# Railbooster_Shield.net
KiCad netlist of a schematic drawn in EAGLE
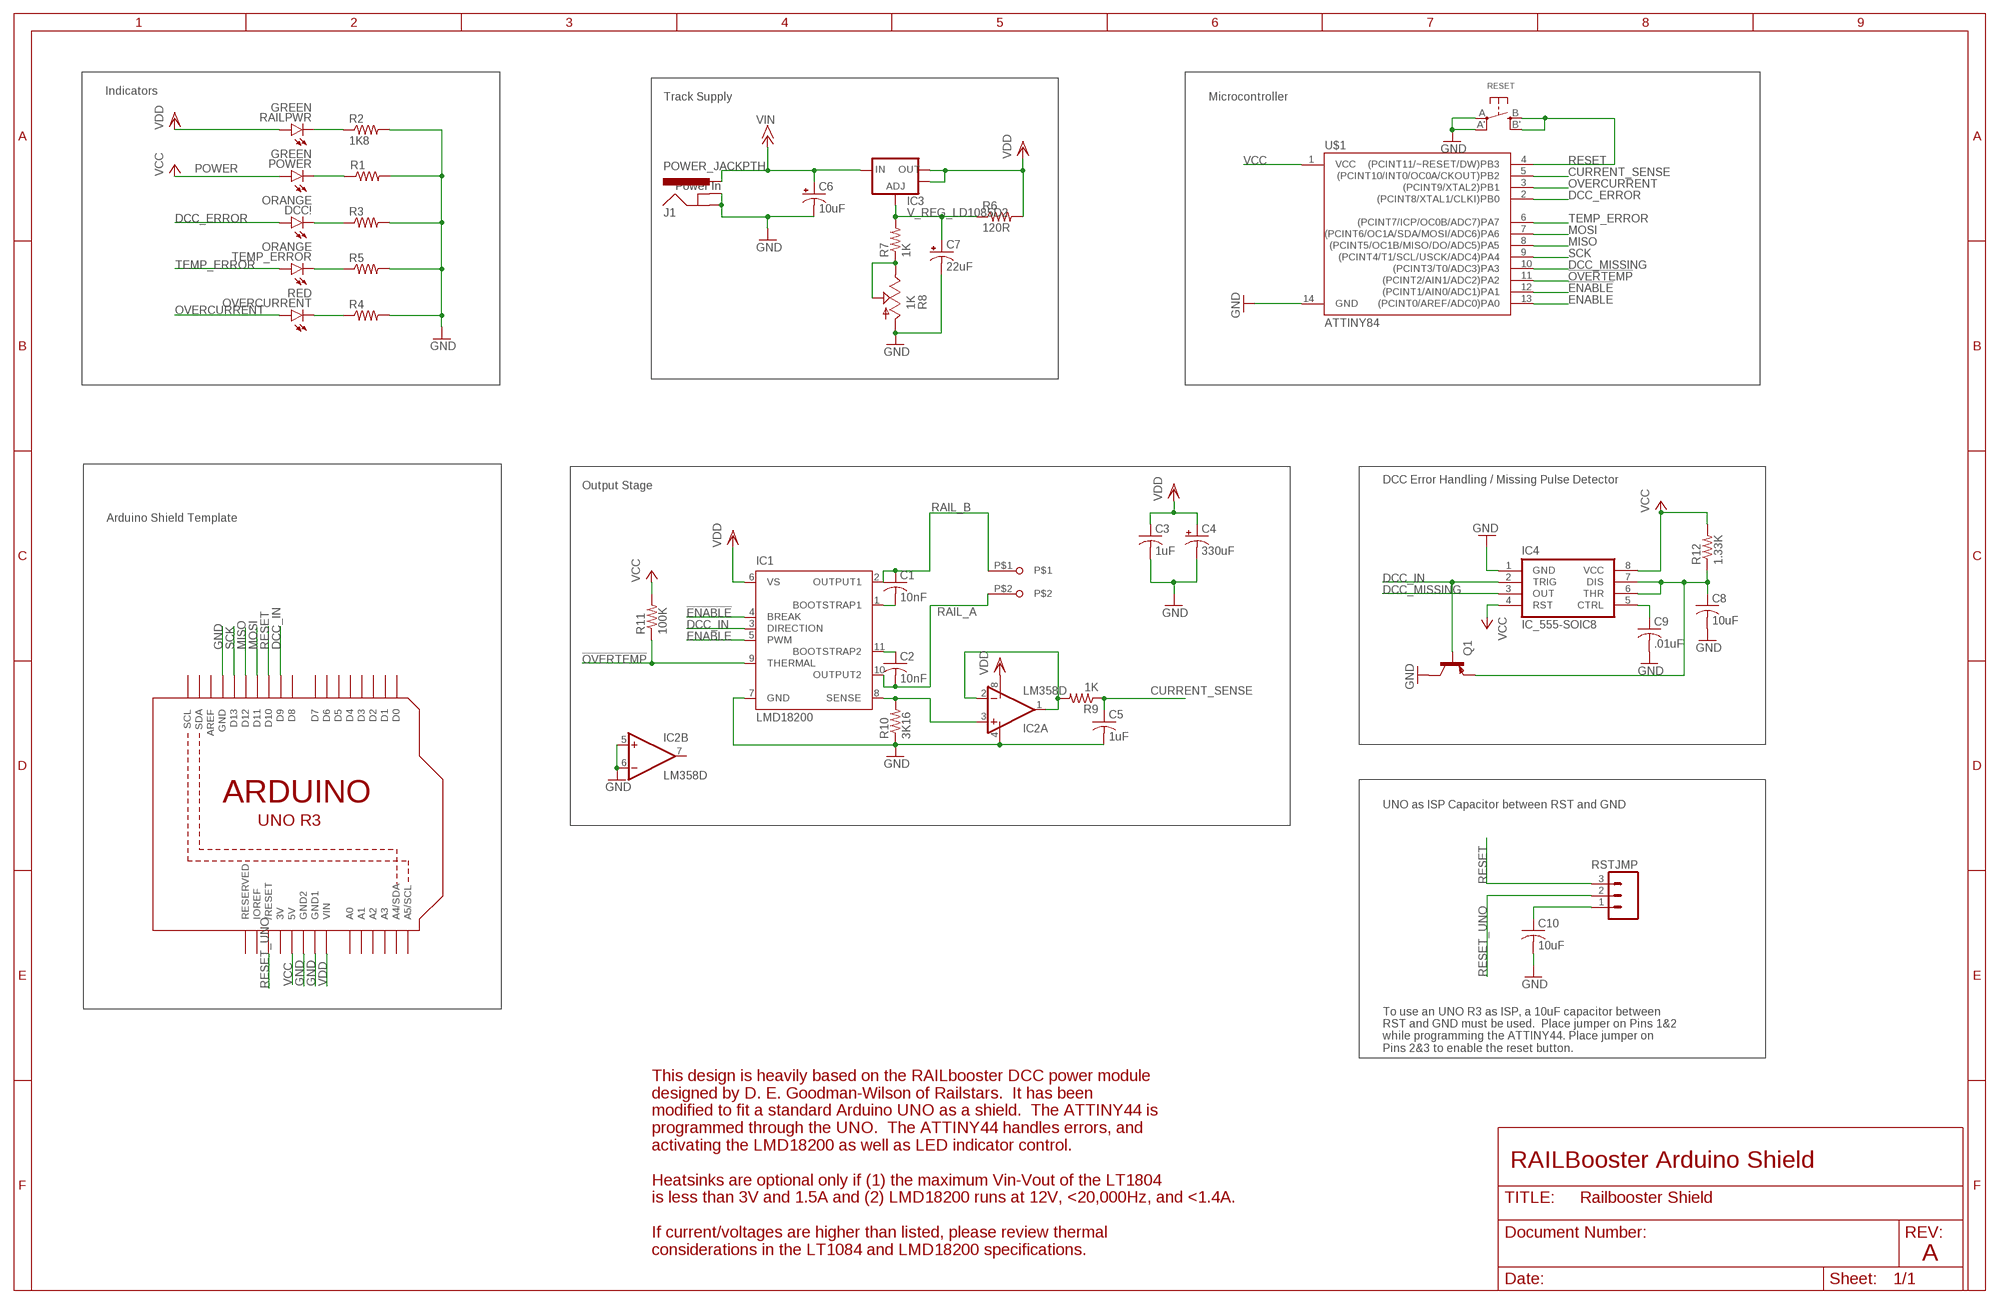
[diagram p0: schematic, sheet 1]

(export (version "E")
  (design (tool "Eeschema 10.0.6"))
  (components
    (comp (ref "C1")
      (value "10nF")
      (footprint "eagle-import:C1206")
      (libsource (lib "eagle-import") (part "C-USC1206"))
    )
    (comp (ref "C2")
      (value "10nF")
      (footprint "eagle-import:C1206")
      (libsource (lib "eagle-import") (part "C-USC1206"))
    )
    (comp (ref "C3")
      (value "1uF")
      (footprint "eagle-import:C1206")
      (libsource (lib "eagle-import") (part "C-USC1206"))
    )
    (comp (ref "C4")
      (value "330uF")
      (footprint "eagle-import:E5-10,5")
      (libsource (lib "eagle-import") (part "CPOL-USE5-10.5"))
    )
    (comp (ref "C5")
      (value "1uF")
      (footprint "eagle-import:C1206")
      (libsource (lib "eagle-import") (part "C-USC1206"))
    )
    (comp (ref "C6")
      (value "10uF")
      (footprint "eagle-import:E2-5")
      (libsource (lib "eagle-import") (part "CPOL-USE2-5"))
    )
    (comp (ref "C7")
      (value "22uF")
      (footprint "eagle-import:E2-5")
      (libsource (lib "eagle-import") (part "CPOL-USE2-5"))
    )
    (comp (ref "C8")
      (value "10uF")
      (footprint "eagle-import:C1206")
      (libsource (lib "eagle-import") (part "C-USC1206"))
    )
    (comp (ref "C9")
      (value ".01uF")
      (footprint "eagle-import:C1206")
      (libsource (lib "eagle-import") (part "C-USC1206"))
    )
    (comp (ref "C10")
      (value "10uF")
      (footprint "eagle-import:C1206")
      (libsource (lib "eagle-import") (part "C-USC1206"))
    )
    (comp (ref "DCC!")
      (value "ORANGE")
      (footprint "eagle-import:LED-1206")
      (libsource (lib "eagle-import") (part "LED1206"))
    )
    (comp (ref "IC1")
      (value "LMD18200")
      (footprint "eagle-import:TO-220-11")
      (libsource (lib "eagle-import") (part "LM18200T"))
    )
    (comp (ref "IC2")
      (value "LM358D")
      (footprint "eagle-import:SO08")
      (libsource (lib "eagle-import") (part "LM358D"))
    )
    (comp (ref "IC3")
      (value "V_REG_LD1085D2")
      (footprint "eagle-import:D2PACK_A")
      (libsource (lib "eagle-import") (part "V_REG_LD1085D2"))
    )
    (comp (ref "IC4")
      (value "IC_555-SOIC8")
      (footprint "eagle-import:SOIC-8")
      (libsource (lib "eagle-import") (part "IC_555-SOIC8"))
    )
    (comp (ref "J1")
      (value "POWER_JACKPTH")
      (footprint "eagle-import:POWER_JACK_PTH")
      (libsource (lib "eagle-import") (part "POWER_JACKPTH"))
    )
    (comp (ref "OVERCURRENT")
      (value "RED")
      (footprint "eagle-import:LED-1206")
      (libsource (lib "eagle-import") (part "LED1206"))
    )
    (comp (ref "POWER")
      (value "GREEN")
      (footprint "eagle-import:LED-1206")
      (libsource (lib "eagle-import") (part "LED1206"))
    )
    (comp (ref "Q1")
      (value "TRANSISTOR_BJT_PNP-SOT-23-BCE")
      (footprint "eagle-import:SOT-23")
      (libsource (lib "eagle-import") (part "TRANSISTOR_BJT_PNP-SOT-23-BCE"))
    )
    (comp (ref "R1")
      (value "RESISTOR1206")
      (footprint "eagle-import:1206")
      (libsource (lib "eagle-import") (part "RESISTOR1206"))
    )
    (comp (ref "R2")
      (value "1K8")
      (footprint "eagle-import:1206")
      (libsource (lib "eagle-import") (part "RESISTOR1206"))
    )
    (comp (ref "R3")
      (value "RESISTOR1206")
      (footprint "eagle-import:1206")
      (libsource (lib "eagle-import") (part "RESISTOR1206"))
    )
    (comp (ref "R4")
      (value "RESISTOR1206")
      (footprint "eagle-import:1206")
      (libsource (lib "eagle-import") (part "RESISTOR1206"))
    )
    (comp (ref "R5")
      (value "RESISTOR1206")
      (footprint "eagle-import:1206")
      (libsource (lib "eagle-import") (part "RESISTOR1206"))
    )
    (comp (ref "R6")
      (value "120R")
      (footprint "eagle-import:1206")
      (libsource (lib "eagle-import") (part "RESISTOR1206"))
    )
    (comp (ref "R7")
      (value "1K")
      (footprint "eagle-import:1206")
      (libsource (lib "eagle-import") (part "RESISTOR1206"))
    )
    (comp (ref "R8")
      (value "1K")
      (footprint "eagle-import:S64W")
      (libsource (lib "eagle-import") (part "TRIM_US-S64W"))
    )
    (comp (ref "R9")
      (value "1K")
      (footprint "eagle-import:1206")
      (libsource (lib "eagle-import") (part "RESISTOR1206"))
    )
    (comp (ref "R10")
      (value "3K16")
      (footprint "eagle-import:1206")
      (libsource (lib "eagle-import") (part "RESISTOR1206"))
    )
    (comp (ref "R11")
      (value "100K")
      (footprint "eagle-import:1206")
      (libsource (lib "eagle-import") (part "RESISTOR1206"))
    )
    (comp (ref "R12")
      (value "1.33K")
      (footprint "eagle-import:1206")
      (libsource (lib "eagle-import") (part "RESISTOR1206"))
    )
    (comp (ref "RAILPWR")
      (value "GREEN")
      (footprint "eagle-import:LED-1206")
      (libsource (lib "eagle-import") (part "LED1206"))
    )
    (comp (ref "RESET")
      (value "SWITCH_TACT_SMT")
      (footprint "eagle-import:EVQ-Q2")
      (libsource (lib "eagle-import") (part "SWITCH_TACT_SMT"))
    )
    (comp (ref "RSTJMP")
      (value "M03PTH")
      (footprint "eagle-import:1X03")
      (libsource (lib "eagle-import") (part "M03PTH"))
    )
    (comp (ref "TEMP_ERROR")
      (value "ORANGE")
      (footprint "eagle-import:LED-1206")
      (libsource (lib "eagle-import") (part "LED1206"))
    )
    (comp (ref "U$1")
      (value "ATTINY84")
      (footprint "eagle-import:SO14")
      (libsource (lib "eagle-import") (part "ATTINY84"))
    )
    (comp (ref "U1")
      (value "ARDUINOR3-DIMENSION")
      (footprint "eagle-import:ARDUINOR3")
      (libsource (lib "eagle-import") (part "ARDUINOR3-DIMENSION"))
    )
    (comp (ref "X4")
      (value "SCREWTERMINAL-5.08-2")
      (footprint "eagle-import:SCREWTERMINAL-5.08-2")
      (libsource (lib "eagle-import") (part "SCREWTERMINAL-5.08-2"))
    )
  )
  (nets
    (net (code "1") (name "/3V") (class "Default")
      (node (ref "U1") (pin "3V") (pinfunction "3V_3V") (pintype "power_in"))
    )
    (net (code "2") (name "/CURRENT_SENSE") (class "Default")
      (node (ref "C5") (pin "1") (pinfunction "1_1") (pintype "passive"))
      (node (ref "R9") (pin "1") (pinfunction "1_1") (pintype "passive"))
      (node (ref "U$1") (pin "5") (pinfunction "(PCINT10/INT0/OC0A/CKOUT)PB2_5") (pintype "bidirectional"))
    )
    (net (code "3") (name "/DCC_ERROR") (class "Default")
      (node (ref "DCC!") (pin "A") (pinfunction "A_A") (pintype "passive"))
      (node (ref "U$1") (pin "2") (pinfunction "(PCINT8/XTAL1/CLKI)PB0_2") (pintype "bidirectional"))
    )
    (net (code "4") (name "/DCC_IN") (class "Default")
      (node (ref "IC1") (pin "3") (pinfunction "DIRECTION_3") (pintype "input"))
      (node (ref "IC4") (pin "2") (pinfunction "TRIG_2") (pintype "input"))
      (node (ref "Q1") (pin "1") (pinfunction "B_1") (pintype "passive"))
      (node (ref "U1") (pin "D9") (pinfunction "D9_D9") (pintype "bidirectional"))
    )
    (net (code "5") (name "/DCC_MISSING") (class "Default")
      (node (ref "IC4") (pin "3") (pinfunction "OUT_3") (pintype "output"))
      (node (ref "U$1") (pin "10") (pinfunction "(PCINT3/T0/ADC3)PA3_10") (pintype "bidirectional"))
    )
    (net (code "6") (name "/ENABLE") (class "Default")
      (node (ref "IC1") (pin "5") (pinfunction "PWM_5") (pintype "input"))
      (node (ref "U$1") (pin "13") (pinfunction "(PCINT0/AREF/ADC0)PA0_13") (pintype "bidirectional"))
    )
    (net (code "7") (name "/MISO") (class "Default")
      (node (ref "U$1") (pin "8") (pinfunction "(PCINT5/OC1B/MISO/DO/ADC5)PA5_8") (pintype "bidirectional"))
      (node (ref "U1") (pin "D12") (pinfunction "D12_D12") (pintype "bidirectional"))
    )
    (net (code "8") (name "/MOSI") (class "Default")
      (node (ref "U$1") (pin "7") (pinfunction "(PCINT6/OC1A/SDA/MOSI/ADC6)PA6_7") (pintype "bidirectional"))
      (node (ref "U1") (pin "D11") (pinfunction "D11_D11") (pintype "bidirectional"))
    )
    (net (code "9") (name "/OVERCURRENT") (class "Default")
      (node (ref "OVERCURRENT") (pin "A") (pinfunction "A_A") (pintype "passive"))
      (node (ref "U$1") (pin "3") (pinfunction "(PCINT9/XTAL2)PB1_3") (pintype "bidirectional"))
    )
    (net (code "10") (name "/RAIL_A") (class "Default")
      (node (ref "C2") (pin "2") (pinfunction "2_2") (pintype "passive"))
      (node (ref "IC1") (pin "10") (pinfunction "OUTPUT2_10") (pintype "output"))
      (node (ref "X4") (pin "P$2") (pinfunction "P$2_P$2") (pintype "bidirectional"))
    )
    (net (code "11") (name "/RAIL_B") (class "Default")
      (node (ref "C1") (pin "1") (pinfunction "1_1") (pintype "passive"))
      (node (ref "IC1") (pin "2") (pinfunction "OUTPUT1_2") (pintype "output"))
      (node (ref "X4") (pin "P$1") (pinfunction "P$1_P$1") (pintype "bidirectional"))
    )
    (net (code "12") (name "/RESET") (class "Default")
      (node (ref "RESET") (pin "B") (pinfunction "S_B") (pintype "passive"))
      (node (ref "RESET") (pin "B'") (pinfunction "S1_B'") (pintype "passive"))
      (node (ref "RSTJMP") (pin "3") (pinfunction "3_3") (pintype "passive"))
      (node (ref "U$1") (pin "4") (pinfunction "(PCINT11/~{RESET/DW})PB3_4") (pintype "bidirectional"))
      (node (ref "U1") (pin "D10") (pinfunction "D10_D10") (pintype "bidirectional"))
    )
    (net (code "13") (name "/RESET_UNO") (class "Default")
      (node (ref "RSTJMP") (pin "2") (pinfunction "2_2") (pintype "passive"))
      (node (ref "U1") (pin "RESET") (pinfunction "/RESET_RESET") (pintype "bidirectional"))
    )
    (net (code "14") (name "/SCK") (class "Default")
      (node (ref "U$1") (pin "9") (pinfunction "(PCINT4/T1/SCL/USCK/ADC4)PA4_9") (pintype "bidirectional"))
      (node (ref "U1") (pin "D13") (pinfunction "D13_D13") (pintype "bidirectional"))
    )
    (net (code "15") (name "/TEMP_ERROR") (class "Default")
      (node (ref "TEMP_ERROR") (pin "A") (pinfunction "A_A") (pintype "passive"))
      (node (ref "U$1") (pin "6") (pinfunction "(PCINT7/ICP/OC0B/ADC7)PA7_6") (pintype "bidirectional"))
    )
    (net (code "16") (name "/~{ENABLE}") (class "Default")
      (node (ref "IC1") (pin "4") (pinfunction "BREAK_4") (pintype "input"))
      (node (ref "U$1") (pin "12") (pinfunction "(PCINT1/AIN0/ADC1)PA1_12") (pintype "bidirectional"))
    )
    (net (code "17") (name "/~{OVERTEMP}") (class "Default")
      (node (ref "IC1") (pin "9") (pinfunction "THERMAL_9") (pintype "output"))
      (node (ref "R11") (pin "1") (pinfunction "1_1") (pintype "passive"))
      (node (ref "U$1") (pin "11") (pinfunction "(PCINT2/AIN1/ADC2)PA2_11") (pintype "bidirectional"))
    )
    (net (code "18") (name "GND") (class "Default")
      (node (ref "C10") (pin "2") (pinfunction "2_2") (pintype "passive"))
      (node (ref "C3") (pin "2") (pinfunction "2_2") (pintype "passive"))
      (node (ref "C4") (pin "-") (pinfunction "-_-") (pintype "passive"))
      (node (ref "C5") (pin "2") (pinfunction "2_2") (pintype "passive"))
      (node (ref "C6") (pin "-") (pinfunction "-_-") (pintype "passive"))
      (node (ref "C7") (pin "-") (pinfunction "-_-") (pintype "passive"))
      (node (ref "C8") (pin "2") (pinfunction "2_2") (pintype "passive"))
      (node (ref "C9") (pin "2") (pinfunction "2_2") (pintype "passive"))
      (node (ref "IC1") (pin "7") (pinfunction "GND_7") (pintype "power_in"))
      (node (ref "IC2") (pin "4") (pinfunction "V-_4") (pintype "power_in"))
      (node (ref "IC2") (pin "5") (pinfunction "+IN_5") (pintype "input"))
      (node (ref "IC2") (pin "6") (pinfunction "-IN_6") (pintype "input"))
      (node (ref "IC4") (pin "1") (pinfunction "GND_1") (pintype "power_in"))
      (node (ref "J1") (pin "GND") (pinfunction "GND_GND") (pintype "bidirectional"))
      (node (ref "J1") (pin "GNDBREAK") (pinfunction "GNDBREAK_GNDBREAK") (pintype "bidirectional"))
      (node (ref "Q1") (pin "2") (pinfunction "C_2") (pintype "passive"))
      (node (ref "R1") (pin "2") (pinfunction "2_2") (pintype "passive"))
      (node (ref "R10") (pin "1") (pinfunction "1_1") (pintype "passive"))
      (node (ref "R2") (pin "2") (pinfunction "2_2") (pintype "passive"))
      (node (ref "R3") (pin "2") (pinfunction "2_2") (pintype "passive"))
      (node (ref "R4") (pin "2") (pinfunction "2_2") (pintype "passive"))
      (node (ref "R5") (pin "2") (pinfunction "2_2") (pintype "passive"))
      (node (ref "R8") (pin "A") (pinfunction "A_A") (pintype "passive"))
      (node (ref "RESET") (pin "A") (pinfunction "P_A") (pintype "passive"))
      (node (ref "RESET") (pin "A'") (pinfunction "P1_A'") (pintype "passive"))
      (node (ref "U$1") (pin "14") (pinfunction "GND_14") (pintype "bidirectional"))
      (node (ref "U1") (pin "GND") (pinfunction "GND_GND") (pintype "power_in"))
      (node (ref "U1") (pin "GND1") (pinfunction "GND1_GND1") (pintype "power_in"))
      (node (ref "U1") (pin "GND2") (pinfunction "GND2_GND2") (pintype "power_in"))
    )
    (net (code "19") (name "Net-(C10-Pad1)") (class "Default")
      (node (ref "C10") (pin "1") (pinfunction "1_1") (pintype "passive"))
      (node (ref "RSTJMP") (pin "1") (pinfunction "1_1") (pintype "passive"))
    )
    (net (code "20") (name "Net-(DCC!-PadC)") (class "Default")
      (node (ref "DCC!") (pin "C") (pinfunction "C_C") (pintype "passive"))
      (node (ref "R3") (pin "1") (pinfunction "1_1") (pintype "passive"))
    )
    (net (code "21") (name "Net-(IC1-BOOTSTRAP1)") (class "Default")
      (node (ref "C1") (pin "2") (pinfunction "2_2") (pintype "passive"))
      (node (ref "IC1") (pin "1") (pinfunction "BOOTSTRAP1_1") (pintype "input"))
    )
    (net (code "22") (name "Net-(IC1-BOOTSTRAP2)") (class "Default")
      (node (ref "C2") (pin "1") (pinfunction "1_1") (pintype "passive"))
      (node (ref "IC1") (pin "11") (pinfunction "BOOTSTRAP2_11") (pintype "input"))
    )
    (net (code "23") (name "Net-(IC1-SENSE)") (class "Default")
      (node (ref "IC1") (pin "8") (pinfunction "SENSE_8") (pintype "output"))
      (node (ref "IC2") (pin "3") (pinfunction "+IN_3") (pintype "input"))
      (node (ref "R10") (pin "2") (pinfunction "2_2") (pintype "passive"))
    )
    (net (code "24") (name "Net-(IC2A--IN)") (class "Default")
      (node (ref "IC2") (pin "1") (pinfunction "OUT_1") (pintype "output"))
      (node (ref "IC2") (pin "2") (pinfunction "-IN_2") (pintype "input"))
      (node (ref "R9") (pin "2") (pinfunction "2_2") (pintype "passive"))
    )
    (net (code "25") (name "Net-(IC3-ADJ)") (class "Default")
      (node (ref "C7") (pin "+") (pinfunction "+_+") (pintype "passive"))
      (node (ref "IC3") (pin "1") (pinfunction "ADJ_1") (pintype "input"))
      (node (ref "R6") (pin "1") (pinfunction "1_1") (pintype "passive"))
      (node (ref "R7") (pin "2") (pinfunction "2_2") (pintype "passive"))
    )
    (net (code "26") (name "Net-(IC4-CTRL)") (class "Default")
      (node (ref "C9") (pin "1") (pinfunction "1_1") (pintype "passive"))
      (node (ref "IC4") (pin "5") (pinfunction "CTRL_5") (pintype "power_in"))
    )
    (net (code "27") (name "Net-(IC4-DIS)") (class "Default")
      (node (ref "C8") (pin "1") (pinfunction "1_1") (pintype "passive"))
      (node (ref "IC4") (pin "6") (pinfunction "THR_6") (pintype "input"))
      (node (ref "IC4") (pin "7") (pinfunction "DIS_7") (pintype "input"))
      (node (ref "Q1") (pin "3") (pinfunction "E_3") (pintype "passive"))
      (node (ref "R12") (pin "1") (pinfunction "1_1") (pintype "passive"))
    )
    (net (code "28") (name "Net-(OVERCURRENT-PadC)") (class "Default")
      (node (ref "OVERCURRENT") (pin "C") (pinfunction "C_C") (pintype "passive"))
      (node (ref "R4") (pin "1") (pinfunction "1_1") (pintype "passive"))
    )
    (net (code "29") (name "Net-(POWER-PadC)") (class "Default")
      (node (ref "POWER") (pin "C") (pinfunction "C_C") (pintype "passive"))
      (node (ref "R1") (pin "1") (pinfunction "1_1") (pintype "passive"))
    )
    (net (code "30") (name "Net-(R2-Pad1)") (class "Default")
      (node (ref "R2") (pin "1") (pinfunction "1_1") (pintype "passive"))
      (node (ref "RAILPWR") (pin "C") (pinfunction "C_C") (pintype "passive"))
    )
    (net (code "31") (name "Net-(R5-Pad1)") (class "Default")
      (node (ref "R5") (pin "1") (pinfunction "1_1") (pintype "passive"))
      (node (ref "TEMP_ERROR") (pin "C") (pinfunction "C_C") (pintype "passive"))
    )
    (net (code "32") (name "Net-(R7-Pad1)") (class "Default")
      (node (ref "R7") (pin "1") (pinfunction "1_1") (pintype "passive"))
      (node (ref "R8") (pin "E") (pinfunction "E_E") (pintype "passive"))
      (node (ref "R8") (pin "S") (pinfunction "S_S") (pintype "passive"))
    )
    (net (code "33") (name "VCC") (class "Default")
      (node (ref "IC4") (pin "4") (pinfunction "RST_4") (pintype "input"))
      (node (ref "IC4") (pin "8") (pinfunction "VCC_8") (pintype "power_in"))
      (node (ref "POWER") (pin "A") (pinfunction "A_A") (pintype "passive"))
      (node (ref "R11") (pin "2") (pinfunction "2_2") (pintype "passive"))
      (node (ref "R12") (pin "2") (pinfunction "2_2") (pintype "passive"))
      (node (ref "U$1") (pin "1") (pinfunction "VCC_1") (pintype "bidirectional"))
      (node (ref "U1") (pin "5V") (pinfunction "5V_5V") (pintype "power_in"))
    )
    (net (code "34") (name "VDD") (class "Default")
      (node (ref "C3") (pin "1") (pinfunction "1_1") (pintype "passive"))
      (node (ref "C4") (pin "+") (pinfunction "+_+") (pintype "passive"))
      (node (ref "IC1") (pin "6") (pinfunction "VS_6") (pintype "power_in"))
      (node (ref "IC2") (pin "8") (pinfunction "V+_8") (pintype "power_in"))
      (node (ref "IC3") (pin "2") (pinfunction "OUT_2") (pintype "output"))
      (node (ref "IC3") (pin "TAB") (pinfunction "OUT_TAB") (pintype "output"))
      (node (ref "R6") (pin "2") (pinfunction "2_2") (pintype "passive"))
      (node (ref "RAILPWR") (pin "A") (pinfunction "A_A") (pintype "passive"))
      (node (ref "U1") (pin "VIN") (pinfunction "VIN_VIN") (pintype "power_in"))
    )
    (net (code "35") (name "VIN") (class "Default")
      (node (ref "C6") (pin "+") (pinfunction "+_+") (pintype "passive"))
      (node (ref "IC3") (pin "3") (pinfunction "IN_3") (pintype "input"))
      (node (ref "J1") (pin "PWR") (pinfunction "PWR_PWR") (pintype "bidirectional"))
    )
    (net (code "36") (name "unconnected-(IC2B-OUT-Pad7)") (class "Default")
      (node (ref "IC2") (pin "7") (pinfunction "OUT_7") (pintype "output"))
    )
    (net (code "37") (name "unconnected-(U1-A4{slash}SDA-PadA4)") (class "Default")
      (node (ref "U1") (pin "A4") (pinfunction "A4/SDA_A4") (pintype "bidirectional"))
    )
    (net (code "38") (name "unconnected-(U1-A5{slash}SCL-PadA5)") (class "Default")
      (node (ref "U1") (pin "A5") (pinfunction "A5/SCL_A5") (pintype "bidirectional"))
    )
    (net (code "39") (name "unconnected-(U1-PadA0)") (class "Default")
      (node (ref "U1") (pin "A0") (pinfunction "A0_A0") (pintype "bidirectional"))
    )
    (net (code "40") (name "unconnected-(U1-PadA1)") (class "Default")
      (node (ref "U1") (pin "A1") (pinfunction "A1_A1") (pintype "bidirectional"))
    )
    (net (code "41") (name "unconnected-(U1-PadA2)") (class "Default")
      (node (ref "U1") (pin "A2") (pinfunction "A2_A2") (pintype "bidirectional"))
    )
    (net (code "42") (name "unconnected-(U1-PadA3)") (class "Default")
      (node (ref "U1") (pin "A3") (pinfunction "A3_A3") (pintype "bidirectional"))
    )
    (net (code "43") (name "unconnected-(U1-PadAREF)") (class "Default")
      (node (ref "U1") (pin "AREF") (pinfunction "AREF_AREF") (pintype "bidirectional"))
    )
    (net (code "44") (name "unconnected-(U1-PadD0)") (class "Default")
      (node (ref "U1") (pin "D0") (pinfunction "D0_D0") (pintype "bidirectional"))
    )
    (net (code "45") (name "unconnected-(U1-PadD1)") (class "Default")
      (node (ref "U1") (pin "D1") (pinfunction "D1_D1") (pintype "bidirectional"))
    )
    (net (code "46") (name "unconnected-(U1-PadD2)") (class "Default")
      (node (ref "U1") (pin "D2") (pinfunction "D2_D2") (pintype "bidirectional"))
    )
    (net (code "47") (name "unconnected-(U1-PadD3)") (class "Default")
      (node (ref "U1") (pin "D3") (pinfunction "D3_D3") (pintype "bidirectional"))
    )
    (net (code "48") (name "unconnected-(U1-PadD4)") (class "Default")
      (node (ref "U1") (pin "D4") (pinfunction "D4_D4") (pintype "bidirectional"))
    )
    (net (code "49") (name "unconnected-(U1-PadD5)") (class "Default")
      (node (ref "U1") (pin "D5") (pinfunction "D5_D5") (pintype "bidirectional"))
    )
    (net (code "50") (name "unconnected-(U1-PadD6)") (class "Default")
      (node (ref "U1") (pin "D6") (pinfunction "D6_D6") (pintype "bidirectional"))
    )
    (net (code "51") (name "unconnected-(U1-PadD7)") (class "Default")
      (node (ref "U1") (pin "D7") (pinfunction "D7_D7") (pintype "bidirectional"))
    )
    (net (code "52") (name "unconnected-(U1-PadD8)") (class "Default")
      (node (ref "U1") (pin "D8") (pinfunction "D8_D8") (pintype "bidirectional"))
    )
    (net (code "53") (name "unconnected-(U1-PadIOREF)") (class "Default")
      (node (ref "U1") (pin "IOREF") (pinfunction "IOREF_IOREF") (pintype "output"))
    )
    (net (code "54") (name "unconnected-(U1-PadRESERVED)") (class "Default")
      (node (ref "U1") (pin "RESERVED") (pinfunction "RESERVED_RESERVED") (pintype "no_connect"))
    )
    (net (code "55") (name "unconnected-(U1-PadSCL)") (class "Default")
      (node (ref "U1") (pin "SCL") (pinfunction "SCL_SCL") (pintype "bidirectional"))
    )
    (net (code "56") (name "unconnected-(U1-PadSDA)") (class "Default")
      (node (ref "U1") (pin "SDA") (pinfunction "SDA_SDA") (pintype "bidirectional"))
    )
  )
)
